# POWER.net
KiCad netlist of a schematic drawn in Altium Designer
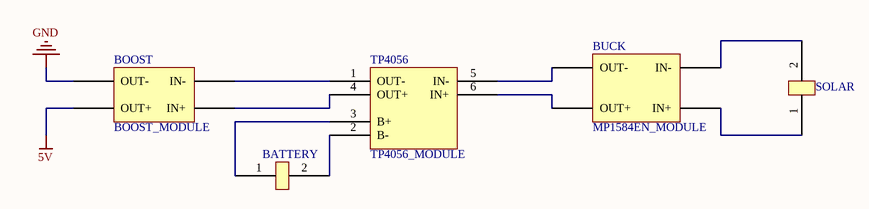
[diagram p0: POWER.SchDoc]

(export (version "E")
  (design (tool "Eeschema 10.0.6"))
  (components
    (comp (ref "BATTERY") (value "PAD_SW") (footprint "PAD_SW") (libsource (lib "") (part "PAD_SW_1")))
    (comp (ref "BOOST")
      (value "BOOST_MODULE")
      (footprint "BOOST_MODULE_MINI")
      (libsource (lib "KHOEMACH_LIB") (part "BOOST_MODULE"))
    )
    (comp (ref "BUCK")
      (value "MP1584EN_MODULE")
      (footprint "MP1584EN_MODULE")
      (libsource (lib "KHOEMACH_LIB") (part "MP1584EN_MODULE"))
    )
    (comp (ref "SOLAR") (value "SOLAR") (footprint "PAD_SW") (libsource (lib "KHOEMACH_LIB") (part "PAD_SW")))
    (comp (ref "TP4056")
      (value "TP4056_MODULE")
      (footprint "TP4056_MODULE")
      (libsource (lib "KHOEMACH_LIB") (part "TP4056_MODULE"))
    )
  )
  (nets
    (net (code "1") (name "5V") (class "Default")
      (node (ref "BOOST") (pin "3") (pinfunction "OUT+_3") (pintype "passive"))
    )
    (net (code "2") (name "GND") (class "Default")
      (node (ref "BOOST") (pin "4") (pinfunction "OUT-_4") (pintype "passive"))
    )
    (net (code "3") (name "Net-(BATTERY-SW1)") (class "Default")
      (node (ref "BATTERY") (pin "1") (pinfunction "SW1_1") (pintype "passive"))
      (node (ref "TP4056") (pin "3") (pinfunction "B+_3") (pintype "passive"))
    )
    (net (code "4") (name "Net-(BATTERY-SW2)") (class "Default")
      (node (ref "BATTERY") (pin "2") (pinfunction "SW2_2") (pintype "passive"))
      (node (ref "TP4056") (pin "2") (pinfunction "B-_2") (pintype "passive"))
    )
    (net (code "5") (name "Net-(BOOST-IN+)") (class "Default")
      (node (ref "BOOST") (pin "1") (pinfunction "IN+_1") (pintype "passive"))
      (node (ref "TP4056") (pin "4") (pinfunction "OUT+_4") (pintype "passive"))
    )
    (net (code "6") (name "Net-(BOOST-IN-)") (class "Default")
      (node (ref "BOOST") (pin "2") (pinfunction "IN-_2") (pintype "passive"))
      (node (ref "TP4056") (pin "1") (pinfunction "OUT-_1") (pintype "passive"))
    )
    (net (code "7") (name "Net-(BUCK-IN+)") (class "Default")
      (node (ref "BUCK") (pin "1") (pinfunction "IN+_1") (pintype "passive"))
      (node (ref "SOLAR") (pin "1") (pinfunction "SW1_1") (pintype "passive"))
    )
    (net (code "8") (name "Net-(BUCK-IN-)") (class "Default")
      (node (ref "BUCK") (pin "2") (pinfunction "IN-_2") (pintype "passive"))
      (node (ref "SOLAR") (pin "2") (pinfunction "SW2_2") (pintype "passive"))
    )
    (net (code "9") (name "Net-(BUCK-OUT+)") (class "Default")
      (node (ref "BUCK") (pin "3") (pinfunction "OUT+_3") (pintype "passive"))
      (node (ref "TP4056") (pin "6") (pinfunction "IN+_6") (pintype "passive"))
    )
    (net (code "10") (name "Net-(BUCK-OUT-)") (class "Default")
      (node (ref "BUCK") (pin "4") (pinfunction "OUT-_4") (pintype "passive"))
      (node (ref "TP4056") (pin "5") (pinfunction "IN-_5") (pintype "passive"))
    )
  )
)
